# attinys2.net
KiCad netlist of a schematic drawn in EAGLE
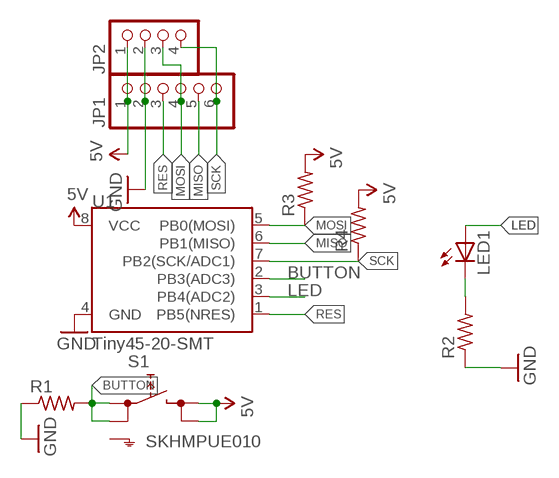
[diagram p0: schematic, sheet 1]

(export (version "E")
  (design (tool "Eeschema 10.0.6"))
  (components
    (comp (ref "JP1")
      (value "PINHD-1X6")
      (footprint "eagle-import:1X06")
      (libsource (lib "eagle-import") (part "PINHD-1X6"))
    )
    (comp (ref "JP2")
      (value "PINHD-1X4")
      (footprint "eagle-import:1X04")
      (libsource (lib "eagle-import") (part "PINHD-1X4"))
    )
    (comp (ref "LED1")
      (value "LEDSML1206")
      (footprint "eagle-import:SML1206")
      (libsource (lib "eagle-import") (part "LEDSML1206"))
    )
    (comp (ref "R1")
      (value "R-US_R1206")
      (footprint "eagle-import:R1206")
      (libsource (lib "eagle-import") (part "R-US_R1206"))
    )
    (comp (ref "R2")
      (value "R-US_R1206")
      (footprint "eagle-import:R1206")
      (libsource (lib "eagle-import") (part "R-US_R1206"))
    )
    (comp (ref "R3")
      (value "R-US_R1206")
      (footprint "eagle-import:R1206")
      (libsource (lib "eagle-import") (part "R-US_R1206"))
    )
    (comp (ref "R4")
      (value "R-US_R1206")
      (footprint "eagle-import:R1206")
      (libsource (lib "eagle-import") (part "R-US_R1206"))
    )
    (comp (ref "S1")
      (value "SKHMPUE010")
      (footprint "eagle-import:SKHMPXE010")
      (libsource (lib "eagle-import") (part "SKHMPE010U"))
    )
    (comp (ref "U1")
      (value "Tiny45-20-SMT")
      (footprint "eagle-import:SO08-EIAJ")
      (libsource (lib "eagle-import") (part "ATTINY45TINY45-20-SMT"))
    )
  )
  (nets
    (net (code "1") (name "5V") (class "Default")
      (node (ref "JP1") (pin "1") (pinfunction "1_1") (pintype "passive"))
      (node (ref "JP2") (pin "1") (pinfunction "1_1") (pintype "passive"))
      (node (ref "R3") (pin "2") (pinfunction "2_2") (pintype "passive"))
      (node (ref "R4") (pin "2") (pinfunction "2_2") (pintype "passive"))
      (node (ref "S1") (pin "3") (pinfunction "2.1_3") (pintype "passive"))
      (node (ref "S1") (pin "4") (pinfunction "2.2_4") (pintype "passive"))
      (node (ref "U1") (pin "8") (pinfunction "VCC_8") (pintype "bidirectional"))
    )
    (net (code "2") (name "BUTTON") (class "Default")
      (node (ref "R1") (pin "2") (pinfunction "2_2") (pintype "passive"))
      (node (ref "S1") (pin "1") (pinfunction "1.1_1") (pintype "passive"))
      (node (ref "S1") (pin "2") (pinfunction "1.2_2") (pintype "passive"))
      (node (ref "U1") (pin "2") (pinfunction "PB3(ADC3)_2") (pintype "bidirectional"))
    )
    (net (code "3") (name "GND") (class "Default")
      (node (ref "JP1") (pin "2") (pinfunction "2_2") (pintype "passive"))
      (node (ref "JP2") (pin "2") (pinfunction "2_2") (pintype "passive"))
      (node (ref "R1") (pin "1") (pinfunction "1_1") (pintype "passive"))
      (node (ref "R2") (pin "1") (pinfunction "1_1") (pintype "passive"))
      (node (ref "U1") (pin "4") (pinfunction "GND_4") (pintype "bidirectional"))
    )
    (net (code "4") (name "LED") (class "Default")
      (node (ref "LED1") (pin "A") (pinfunction "A_A") (pintype "passive"))
      (node (ref "U1") (pin "3") (pinfunction "PB4(ADC2)_3") (pintype "bidirectional"))
    )
    (net (code "5") (name "MISO") (class "Default")
      (node (ref "JP1") (pin "5") (pinfunction "5_5") (pintype "passive"))
      (node (ref "U1") (pin "6") (pinfunction "PB1(MISO)_6") (pintype "bidirectional"))
    )
    (net (code "6") (name "MOSI") (class "Default")
      (node (ref "JP1") (pin "4") (pinfunction "4_4") (pintype "passive"))
      (node (ref "JP2") (pin "3") (pinfunction "3_3") (pintype "passive"))
      (node (ref "R3") (pin "1") (pinfunction "1_1") (pintype "passive"))
      (node (ref "U1") (pin "5") (pinfunction "PB0(MOSI)_5") (pintype "bidirectional"))
    )
    (net (code "7") (name "Net-(LED1-PadC)") (class "Default")
      (node (ref "LED1") (pin "C") (pinfunction "C_C") (pintype "passive"))
      (node (ref "R2") (pin "2") (pinfunction "2_2") (pintype "passive"))
    )
    (net (code "8") (name "RES") (class "Default")
      (node (ref "JP1") (pin "3") (pinfunction "3_3") (pintype "passive"))
      (node (ref "U1") (pin "1") (pinfunction "PB5(NRES)_1") (pintype "bidirectional"))
    )
    (net (code "9") (name "SCK") (class "Default")
      (node (ref "JP1") (pin "6") (pinfunction "6_6") (pintype "passive"))
      (node (ref "JP2") (pin "4") (pinfunction "4_4") (pintype "passive"))
      (node (ref "R4") (pin "1") (pinfunction "1_1") (pintype "passive"))
      (node (ref "U1") (pin "7") (pinfunction "PB2(SCK/ADC1)_7") (pintype "bidirectional"))
    )
    (net (code "10") (name "unconnected-(S1-SH-Pad5)") (class "Default")
      (node (ref "S1") (pin "5") (pinfunction "SH_5") (pintype "passive"))
    )
  )
)
